# Adapter_V6.net
KiCad netlist of a schematic drawn in EAGLE
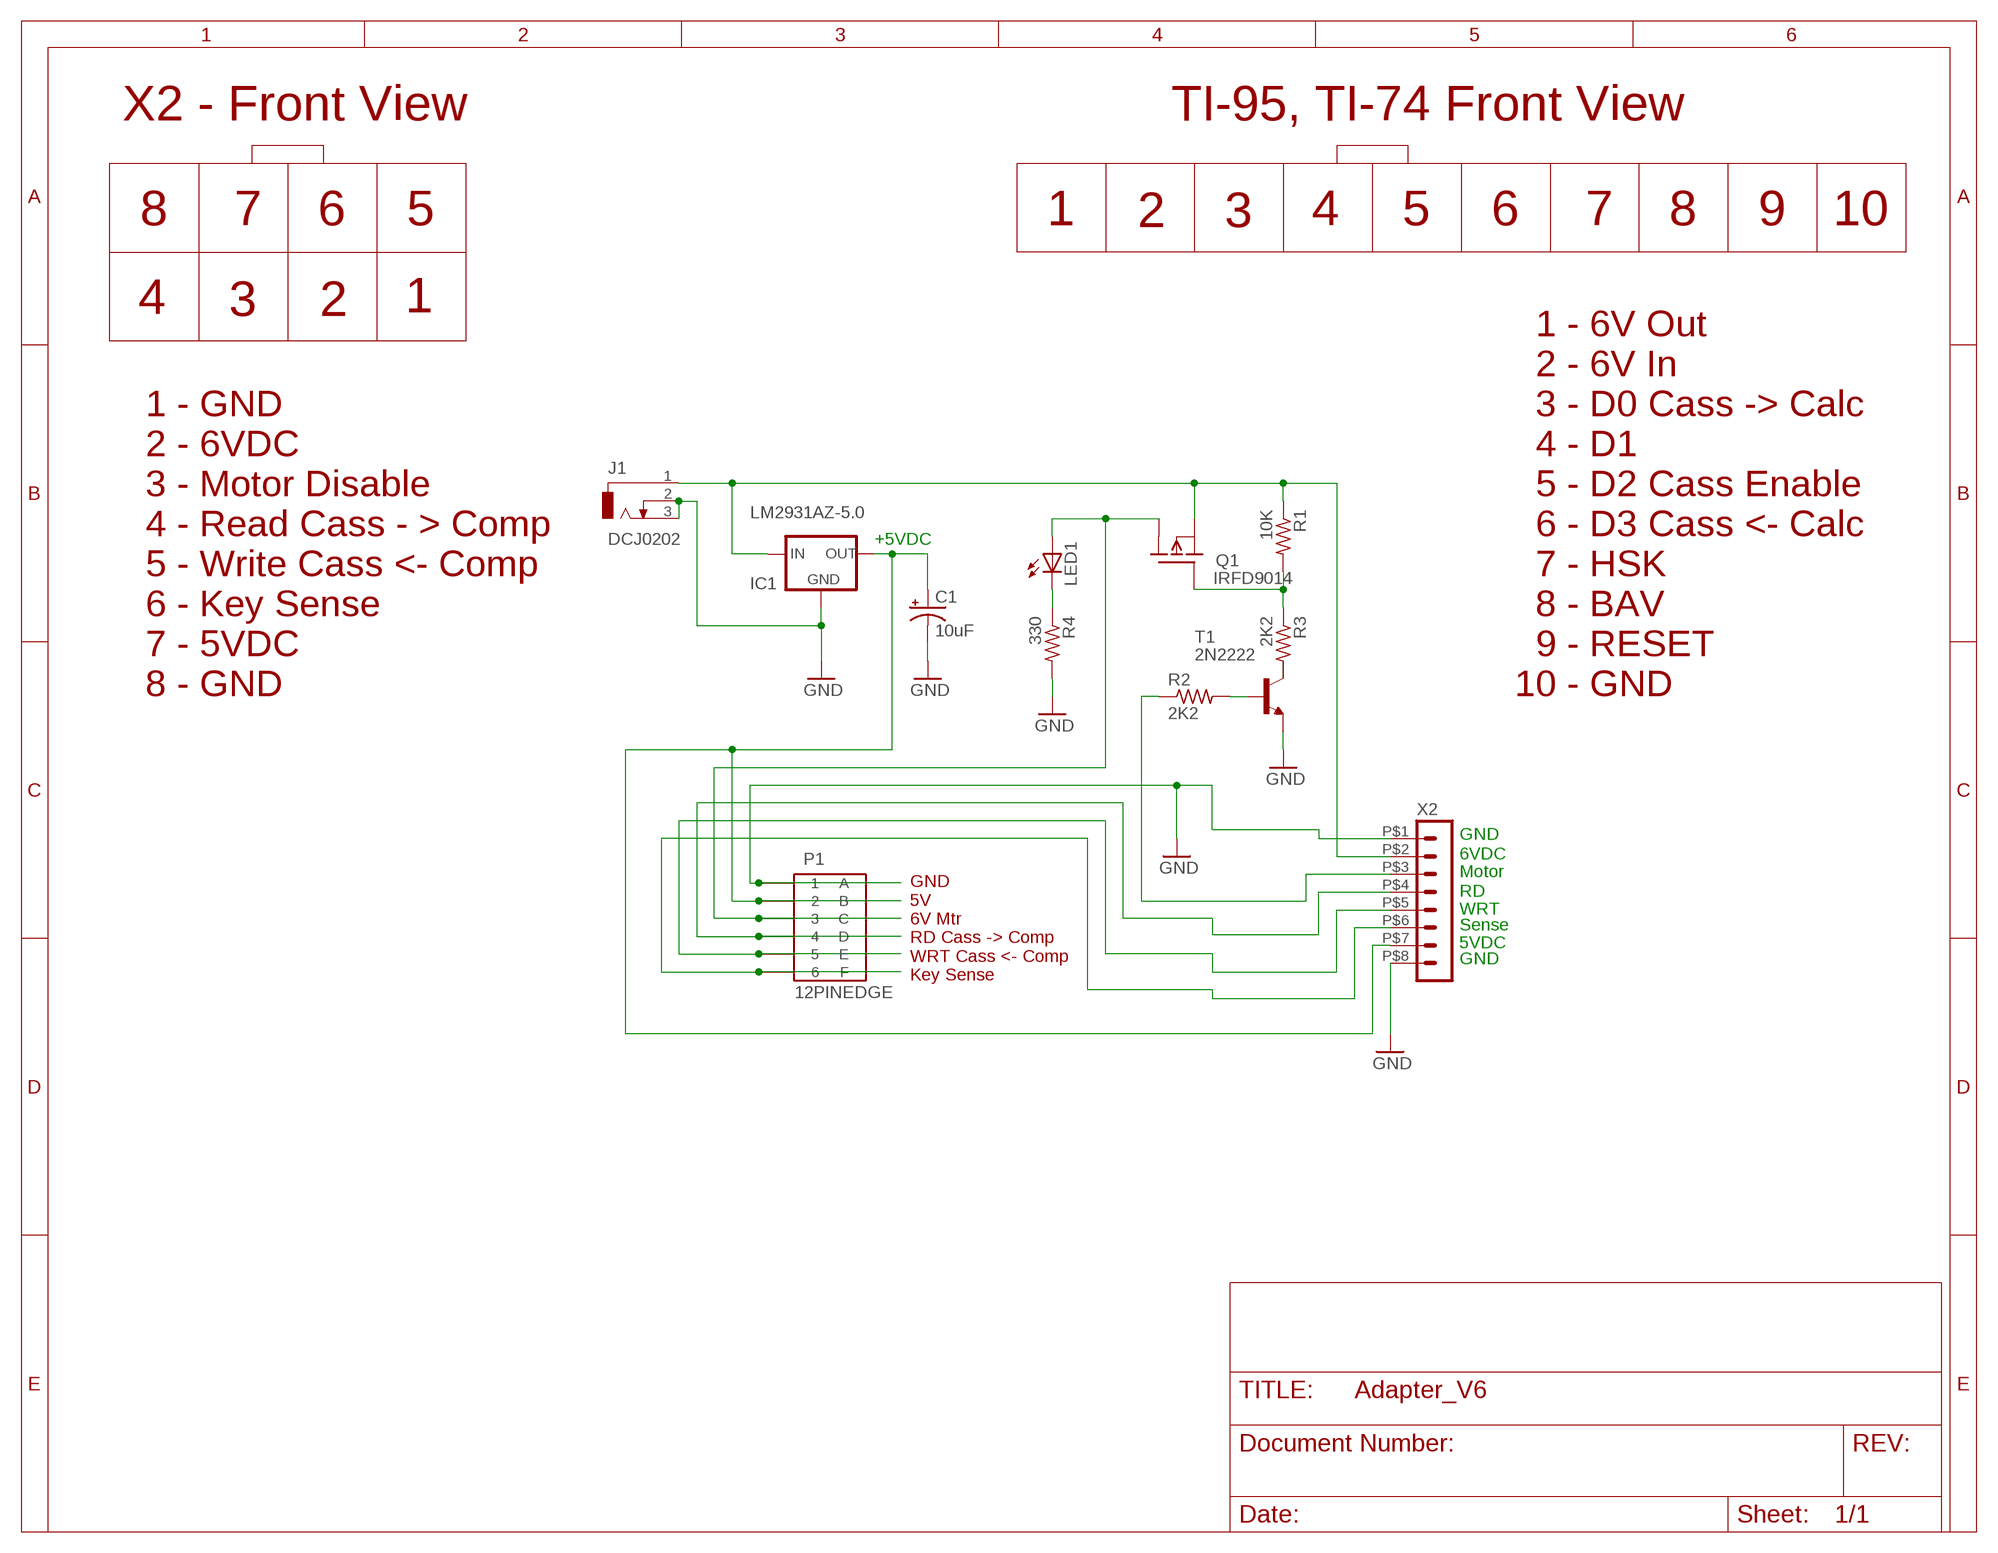
[diagram p0: schematic, sheet 1]

(export (version "E")
  (design (tool "Eeschema 10.0.6"))
  (components
    (comp (ref "C1")
      (value "10uF")
      (footprint "eagle-import:E1,8-4")
      (libsource (lib "eagle-import") (part "CPOL-USE1.8-4"))
    )
    (comp (ref "IC1")
      (value "LM2931AZ-5.0")
      (footprint "eagle-import:TO92")
      (libsource (lib "eagle-import") (part "LM2931?AZ-5.0"))
    )
    (comp (ref "J1")
      (value "DCJ0202")
      (footprint "eagle-import:DCJ0202")
      (libsource (lib "eagle-import") (part "DCJ0202"))
    )
    (comp (ref "LED1")
      (value "LED5MM")
      (footprint "eagle-import:LED5MM")
      (libsource (lib "eagle-import") (part "LED5MM"))
    )
    (comp (ref "P1")
      (value "12PINEDGE")
      (footprint "eagle-import:12PINEDGE")
      (libsource (lib "eagle-import") (part "12PINEDGE"))
    )
    (comp (ref "Q1")
      (value "IRFD9014")
      (footprint "eagle-import:DIL04")
      (libsource (lib "eagle-import") (part "IRFD9014"))
    )
    (comp (ref "R1")
      (value "10K")
      (footprint "eagle-import:0207_10")
      (libsource (lib "eagle-import") (part "R-US_0207/10"))
    )
    (comp (ref "R2")
      (value "2K2")
      (footprint "eagle-import:0207_10")
      (libsource (lib "eagle-import") (part "R-US_0207/10"))
    )
    (comp (ref "R3")
      (value "2K2")
      (footprint "eagle-import:0207_10")
      (libsource (lib "eagle-import") (part "R-US_0207/10"))
    )
    (comp (ref "R4")
      (value "330")
      (footprint "eagle-import:0207_10")
      (libsource (lib "eagle-import") (part "R-US_0207/10"))
    )
    (comp (ref "T1")
      (value "2N2222")
      (footprint "eagle-import:TO18")
      (libsource (lib "eagle-import") (part "2N2222"))
    )
    (comp (ref "X2")
      (value "HEADER_POS8_43045-0800")
      (footprint "eagle-import:43045-0800")
      (libsource (lib "eagle-import") (part "HEADER_POS8_?43045-0800"))
    )
  )
  (nets
    (net (code "1") (name "GND") (class "Default")
      (node (ref "C1") (pin "-") (pinfunction "-_-") (pintype "passive"))
      (node (ref "IC1") (pin "2") (pinfunction "GND_2") (pintype "input"))
      (node (ref "J1") (pin "2") (pinfunction "2_2") (pintype "passive"))
      (node (ref "J1") (pin "3") (pinfunction "3_3") (pintype "passive"))
      (node (ref "P1") (pin "1") (pinfunction "1_1") (pintype "passive"))
      (node (ref "P1") (pin "A") (pinfunction "A_A") (pintype "passive"))
      (node (ref "R4") (pin "2") (pinfunction "2_2") (pintype "passive"))
      (node (ref "T1") (pin "1") (pinfunction "E_1") (pintype "passive"))
      (node (ref "X2") (pin "P$1") (pinfunction "1_P$1") (pintype "passive"))
      (node (ref "X2") (pin "P$8") (pinfunction "8_P$8") (pintype "passive"))
    )
    (net (code "2") (name "Net-(IC1-IN)") (class "Default")
      (node (ref "IC1") (pin "3") (pinfunction "IN_3") (pintype "input"))
      (node (ref "J1") (pin "1") (pinfunction "1_1") (pintype "passive"))
      (node (ref "Q1") (pin "2") (pinfunction "S_2") (pintype "passive"))
      (node (ref "R1") (pin "1") (pinfunction "1_1") (pintype "passive"))
      (node (ref "X2") (pin "P$2") (pinfunction "2_P$2") (pintype "passive"))
    )
    (net (code "3") (name "Net-(IC1-OUT)") (class "Default")
      (node (ref "C1") (pin "+") (pinfunction "+_+") (pintype "passive"))
      (node (ref "IC1") (pin "1") (pinfunction "OUT_1") (pintype "passive"))
      (node (ref "P1") (pin "2") (pinfunction "2_2") (pintype "passive"))
      (node (ref "P1") (pin "B") (pinfunction "B_B") (pintype "passive"))
      (node (ref "X2") (pin "P$7") (pinfunction "7_P$7") (pintype "passive"))
    )
    (net (code "4") (name "Net-(LED1-C)") (class "Default")
      (node (ref "LED1") (pin "K") (pinfunction "C_K") (pintype "passive"))
      (node (ref "R4") (pin "1") (pinfunction "1_1") (pintype "passive"))
    )
    (net (code "5") (name "Net-(Q1-D1)") (class "Default")
      (node (ref "LED1") (pin "A") (pinfunction "A_A") (pintype "passive"))
      (node (ref "P1") (pin "3") (pinfunction "3_3") (pintype "passive"))
      (node (ref "P1") (pin "C") (pinfunction "C_C") (pintype "passive"))
      (node (ref "Q1") (pin "3") (pinfunction "D1_3") (pintype "passive"))
    )
    (net (code "6") (name "Net-(Q1-G)") (class "Default")
      (node (ref "Q1") (pin "1") (pinfunction "G_1") (pintype "passive"))
      (node (ref "R1") (pin "2") (pinfunction "2_2") (pintype "passive"))
      (node (ref "R3") (pin "1") (pinfunction "1_1") (pintype "passive"))
    )
    (net (code "7") (name "Net-(T1-B)") (class "Default")
      (node (ref "R2") (pin "2") (pinfunction "2_2") (pintype "passive"))
      (node (ref "T1") (pin "2") (pinfunction "B_2") (pintype "passive"))
    )
    (net (code "8") (name "Net-(T1-C)") (class "Default")
      (node (ref "R3") (pin "2") (pinfunction "2_2") (pintype "passive"))
      (node (ref "T1") (pin "3") (pinfunction "C_3") (pintype "passive"))
    )
    (net (code "9") (name "Net-(X2-3)") (class "Default")
      (node (ref "R2") (pin "1") (pinfunction "1_1") (pintype "passive"))
      (node (ref "X2") (pin "P$3") (pinfunction "3_P$3") (pintype "passive"))
    )
    (net (code "10") (name "Net-(X2-4)") (class "Default")
      (node (ref "P1") (pin "4") (pinfunction "4_4") (pintype "passive"))
      (node (ref "P1") (pin "D") (pinfunction "D_D") (pintype "passive"))
      (node (ref "X2") (pin "P$4") (pinfunction "4_P$4") (pintype "passive"))
    )
    (net (code "11") (name "Net-(X2-5)") (class "Default")
      (node (ref "P1") (pin "5") (pinfunction "5_5") (pintype "passive"))
      (node (ref "P1") (pin "E") (pinfunction "E_E") (pintype "passive"))
      (node (ref "X2") (pin "P$5") (pinfunction "5_P$5") (pintype "passive"))
    )
    (net (code "12") (name "Net-(X2-6)") (class "Default")
      (node (ref "P1") (pin "6") (pinfunction "6_6") (pintype "passive"))
      (node (ref "P1") (pin "F") (pinfunction "F_F") (pintype "passive"))
      (node (ref "X2") (pin "P$6") (pinfunction "6_P$6") (pintype "passive"))
    )
    (net (code "13") (name "unconnected-(Q1-D-Pad4)") (class "Default")
      (node (ref "Q1") (pin "4") (pinfunction "D_4") (pintype "passive"))
    )
  )
)
